# imu-6dof_tof_board.net
KiCad netlist of a schematic drawn in EAGLE
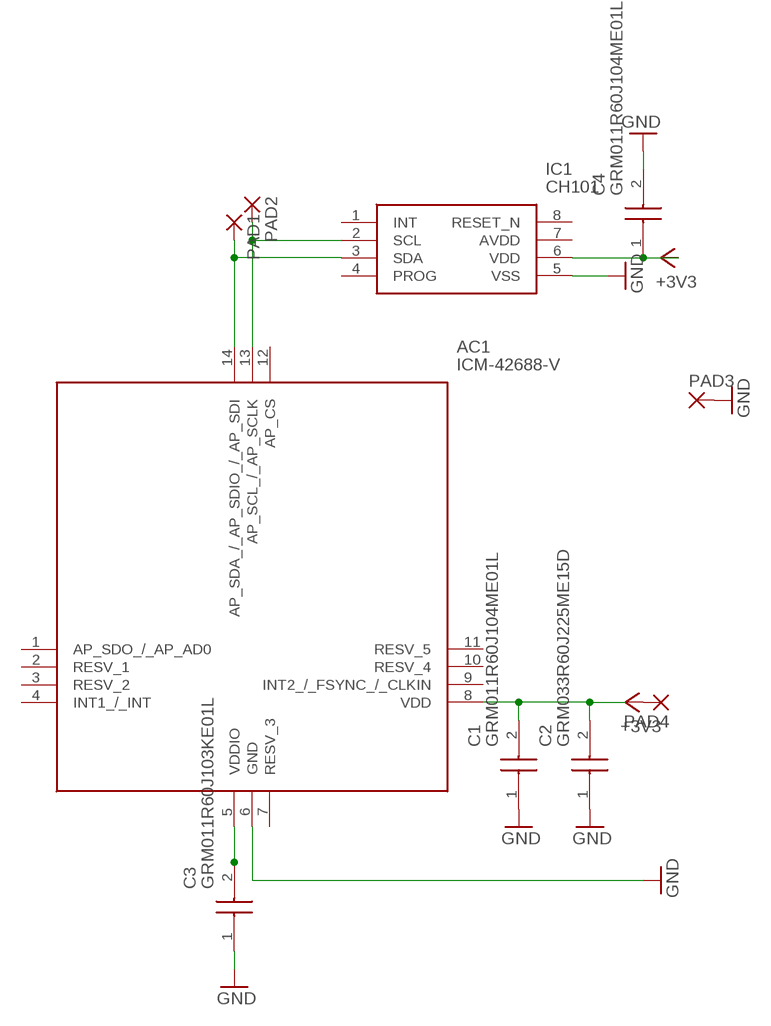
[diagram p0: schematic, sheet 1]

(export (version "E")
  (design (tool "Eeschema 10.0.6"))
  (components
    (comp (ref "AC1")
      (value "ICM-42688-V")
      (footprint "eagle-import:IIM42352")
      (fields (field (name "MOUSER_PART_NUMBER") "410-ICM-42688-V"))
      (libsource (lib "eagle-import") (part "ICM-42688-V"))
    )
    (comp (ref "C1")
      (value "GRM011R60J104ME01L")
      (footprint "eagle-import:CAPC0201X14N")
      (fields (field (name "MOUSER_PART_NUMBER") "81-GRM011R60J104ME1L"))
      (libsource (lib "eagle-import") (part "GRM011R60J104ME01L"))
    )
    (comp (ref "C2")
      (value "GRM033R60J225ME15D")
      (footprint "eagle-import:CAPC0603X33N")
      (fields (field (name "MOUSER_PART_NUMBER") "81-GRM033R60J225ME5D"))
      (libsource (lib "eagle-import") (part "GRM033R60J225ME15D"))
    )
    (comp (ref "C3")
      (value "GRM011R60J103KE01L")
      (footprint "eagle-import:CAPC0201X14N")
      (libsource (lib "eagle-import") (part "GRM011R60J103KE01L"))
    )
    (comp (ref "C4")
      (value "GRM011R60J104ME01L")
      (footprint "eagle-import:CAPC0201X14N")
      (fields (field (name "MOUSER_PART_NUMBER") "81-GRM011R60J104ME1L"))
      (libsource (lib "eagle-import") (part "GRM011R60J104ME01L"))
    )
    (comp (ref "IC1")
      (value "CH101")
      (footprint "eagle-import:CH101")
      (libsource (lib "eagle-import") (part "CH101"))
    )
    (comp (ref "PAD1")
      (value "SMD2")
      (footprint "eagle-import:SMD1,27-2,54")
      (libsource (lib "eagle-import") (part "SMD2"))
    )
    (comp (ref "PAD2")
      (value "SMD2")
      (footprint "eagle-import:SMD1,27-2,54")
      (libsource (lib "eagle-import") (part "SMD2"))
    )
    (comp (ref "PAD3")
      (value "SMD2")
      (footprint "eagle-import:SMD1,27-2,54")
      (libsource (lib "eagle-import") (part "SMD2"))
    )
    (comp (ref "PAD4")
      (value "SMD2")
      (footprint "eagle-import:SMD1,27-2,54")
      (libsource (lib "eagle-import") (part "SMD2"))
    )
  )
  (nets
    (net (code "1") (name "+3V3") (class "Default")
      (node (ref "C4") (pin "1") (pinfunction "1_1") (pintype "bidirectional"))
      (node (ref "IC1") (pin "6") (pinfunction "VDD_6") (pintype "bidirectional"))
      (node (ref "PAD4") (pin "1") (pinfunction "P_1") (pintype "passive"))
    )
    (net (code "2") (name "GND") (class "Default")
      (node (ref "AC1") (pin "6") (pinfunction "GND_6") (pintype "bidirectional"))
      (node (ref "C1") (pin "1") (pinfunction "1_1") (pintype "bidirectional"))
      (node (ref "C2") (pin "1") (pinfunction "1_1") (pintype "bidirectional"))
      (node (ref "C3") (pin "1") (pinfunction "1_1") (pintype "bidirectional"))
      (node (ref "C4") (pin "2") (pinfunction "2_2") (pintype "bidirectional"))
      (node (ref "IC1") (pin "5") (pinfunction "VSS_5") (pintype "bidirectional"))
      (node (ref "PAD3") (pin "1") (pinfunction "P_1") (pintype "passive"))
    )
    (net (code "3") (name "Net-(AC1-AP_SCL_{slash}_AP_SCLK)") (class "Default")
      (node (ref "AC1") (pin "13") (pinfunction "AP_SCL_/_AP_SCLK_13") (pintype "bidirectional"))
      (node (ref "IC1") (pin "2") (pinfunction "SCL_2") (pintype "bidirectional"))
      (node (ref "PAD2") (pin "1") (pinfunction "P_1") (pintype "passive"))
    )
    (net (code "4") (name "Net-(AC1-AP_SDA_{slash}_AP_SDIO_{slash}_AP_SDI)") (class "Default")
      (node (ref "AC1") (pin "14") (pinfunction "AP_SDA_/_AP_SDIO_/_AP_SDI_14") (pintype "bidirectional"))
      (node (ref "IC1") (pin "3") (pinfunction "SDA_3") (pintype "bidirectional"))
      (node (ref "PAD1") (pin "1") (pinfunction "P_1") (pintype "passive"))
    )
    (net (code "5") (name "Net-(AC1-VDD)") (class "Default")
      (node (ref "AC1") (pin "8") (pinfunction "VDD_8") (pintype "bidirectional"))
      (node (ref "C1") (pin "2") (pinfunction "2_2") (pintype "bidirectional"))
      (node (ref "C2") (pin "2") (pinfunction "2_2") (pintype "bidirectional"))
    )
    (net (code "6") (name "Net-(AC1-VDDIO)") (class "Default")
      (node (ref "AC1") (pin "5") (pinfunction "VDDIO_5") (pintype "bidirectional"))
      (node (ref "C3") (pin "2") (pinfunction "2_2") (pintype "bidirectional"))
    )
    (net (code "7") (name "unconnected-(AC1-AP_CS-Pad12)") (class "Default")
      (node (ref "AC1") (pin "12") (pinfunction "AP_CS_12") (pintype "bidirectional"))
    )
    (net (code "8") (name "unconnected-(AC1-AP_SDO_{slash}_AP_AD0-Pad1)") (class "Default")
      (node (ref "AC1") (pin "1") (pinfunction "AP_SDO_/_AP_AD0_1") (pintype "bidirectional"))
    )
    (net (code "9") (name "unconnected-(AC1-INT1_{slash}_INT-Pad4)") (class "Default")
      (node (ref "AC1") (pin "4") (pinfunction "INT1_/_INT_4") (pintype "bidirectional"))
    )
    (net (code "10") (name "unconnected-(AC1-INT2_{slash}_FSYNC_{slash}_CLKIN-Pad9)") (class "Default")
      (node (ref "AC1") (pin "9") (pinfunction "INT2_/_FSYNC_/_CLKIN_9") (pintype "bidirectional"))
    )
    (net (code "11") (name "unconnected-(AC1-RESV_1-Pad2)") (class "Default")
      (node (ref "AC1") (pin "2") (pinfunction "RESV_1_2") (pintype "bidirectional"))
    )
    (net (code "12") (name "unconnected-(AC1-RESV_2-Pad3)") (class "Default")
      (node (ref "AC1") (pin "3") (pinfunction "RESV_2_3") (pintype "bidirectional"))
    )
    (net (code "13") (name "unconnected-(AC1-RESV_3-Pad7)") (class "Default")
      (node (ref "AC1") (pin "7") (pinfunction "RESV_3_7") (pintype "bidirectional"))
    )
    (net (code "14") (name "unconnected-(AC1-RESV_4-Pad10)") (class "Default")
      (node (ref "AC1") (pin "10") (pinfunction "RESV_4_10") (pintype "bidirectional"))
    )
    (net (code "15") (name "unconnected-(AC1-RESV_5-Pad11)") (class "Default")
      (node (ref "AC1") (pin "11") (pinfunction "RESV_5_11") (pintype "bidirectional"))
    )
    (net (code "16") (name "unconnected-(IC1-AVDD-Pad7)") (class "Default")
      (node (ref "IC1") (pin "7") (pinfunction "AVDD_7") (pintype "bidirectional"))
    )
    (net (code "17") (name "unconnected-(IC1-INT-Pad1)") (class "Default")
      (node (ref "IC1") (pin "1") (pinfunction "INT_1") (pintype "bidirectional"))
    )
    (net (code "18") (name "unconnected-(IC1-PROG-Pad4)") (class "Default")
      (node (ref "IC1") (pin "4") (pinfunction "PROG_4") (pintype "bidirectional"))
    )
    (net (code "19") (name "unconnected-(IC1-RESET_N-Pad8)") (class "Default")
      (node (ref "IC1") (pin "8") (pinfunction "RESET_N_8") (pintype "bidirectional"))
    )
  )
)
